# frutir.net
KiCad netlist of a schematic drawn in EAGLE
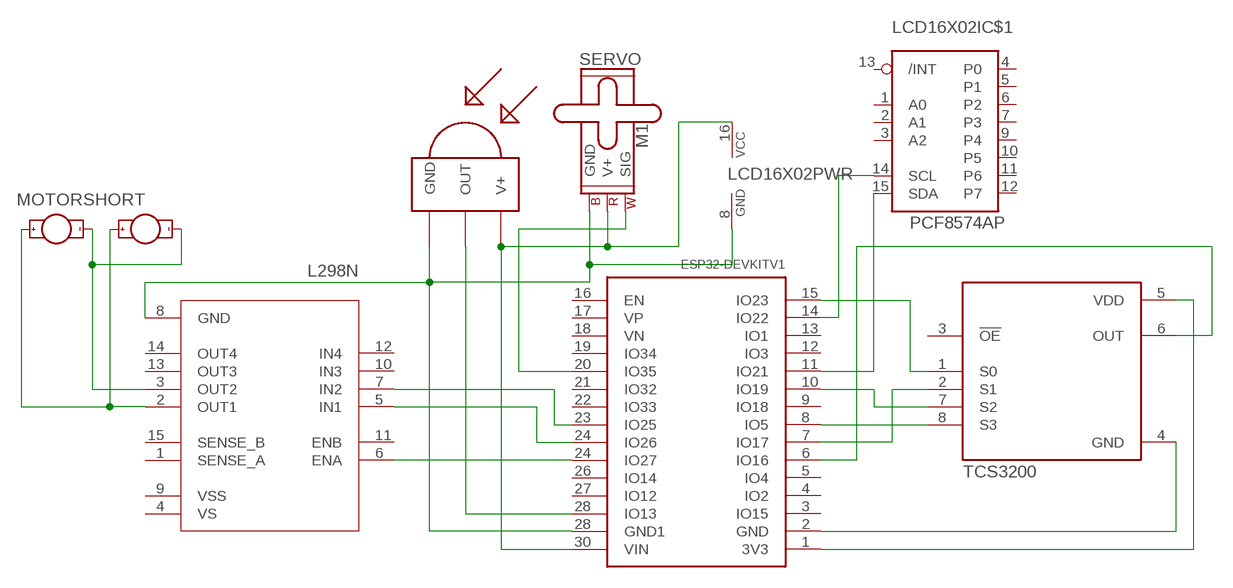
[diagram p0: schematic, sheet 1]

(export (version "E")
  (design (tool "Eeschema 10.0.6"))
  (components
    (comp (ref "LCD16X02")
      (value "PCF8574AP")
      (footprint "eagle-import:DIL16")
      (libsource (lib "eagle-import") (part "PCF8574AP"))
    )
    (comp (ref "M1")
      (value "SERVO")
      (footprint "eagle-import:1X03")
      (libsource (lib "eagle-import") (part "SERVO"))
    )
    (comp (ref "M2")
      (value "MOTORSHORT")
      (footprint "eagle-import:VIBE-MOTOR-10MM-SMD")
      (libsource (lib "eagle-import") (part "MOTORSHORT"))
    )
    (comp (ref "M3")
      (value "MOTORSHORT")
      (footprint "eagle-import:VIBE-MOTOR-10MM-SMD")
      (libsource (lib "eagle-import") (part "MOTORSHORT"))
    )
    (comp (ref "U$1")
      (value "ESP32DEVKITV1")
      (footprint "eagle-import:ESP32-DEVKITV1")
      (libsource (lib "eagle-import") (part "ESP32DEVKITV1"))
    )
    (comp (ref "U$2")
      (value "TSOP1830")
      (footprint "eagle-import:TSOP18XX")
      (libsource (lib "eagle-import") (part "TSOP1830"))
    )
    (comp (ref "U1")
      (value "TCS3200")
      (footprint "eagle-import:SOIC127P600X175-8N")
      (fields (field (name "MF") "ams"))
      (libsource (lib "eagle-import") (part "TCS3200"))
    )
    (comp (ref "U2")
      (value "L298N")
      (footprint "eagle-import:TO127P2020X500X2100-15")
      (fields (field (name "MF") "STMicroelectronics"))
      (libsource (lib "eagle-import") (part "L298N"))
    )
  )
  (nets
    (net (code "1") (name "/VS") (class "Default")
      (node (ref "U2") (pin "4") (pinfunction "VS_4") (pintype "power_in"))
    )
    (net (code "2") (name "Net-(LCD16X02A-SCL)") (class "Default")
      (node (ref "LCD16X02") (pin "14") (pinfunction "SCL_14") (pintype "input"))
      (node (ref "U$1") (pin "14") (pinfunction "IO22_14") (pintype "bidirectional"))
    )
    (net (code "3") (name "Net-(LCD16X02A-SDA)") (class "Default")
      (node (ref "LCD16X02") (pin "15") (pinfunction "SDA_15") (pintype "bidirectional"))
      (node (ref "U$1") (pin "11") (pinfunction "IO21_11") (pintype "bidirectional"))
    )
    (net (code "4") (name "Net-(LCD16X02B-GND)") (class "Default")
      (node (ref "LCD16X02") (pin "8") (pinfunction "GND_8") (pintype "power_in"))
      (node (ref "M1") (pin "3") (pinfunction "GND_3") (pintype "bidirectional"))
      (node (ref "U$1") (pin "28") (pinfunction "GND1_28") (pintype "bidirectional"))
      (node (ref "U$2") (pin "GND") (pinfunction "GND_GND") (pintype "bidirectional"))
      (node (ref "U2") (pin "8") (pinfunction "GND_8") (pintype "power_in"))
    )
    (net (code "5") (name "Net-(LCD16X02B-VCC)") (class "Default")
      (node (ref "LCD16X02") (pin "16") (pinfunction "VCC_16") (pintype "power_in"))
      (node (ref "M1") (pin "2") (pinfunction "V+_2") (pintype "bidirectional"))
      (node (ref "U$1") (pin "30") (pinfunction "VIN_30") (pintype "bidirectional"))
      (node (ref "U$2") (pin "VCC") (pinfunction "V+_VCC") (pintype "bidirectional"))
    )
    (net (code "6") (name "Net-(M1-SIG)") (class "Default")
      (node (ref "M1") (pin "1") (pinfunction "SIG_1") (pintype "bidirectional"))
      (node (ref "U$1") (pin "20") (pinfunction "IO35_20") (pintype "bidirectional"))
    )
    (net (code "7") (name "Net-(U$1-3V3)") (class "Default")
      (node (ref "U$1") (pin "1") (pinfunction "3V3_1") (pintype "bidirectional"))
      (node (ref "U1") (pin "5") (pinfunction "VDD_5") (pintype "power_in"))
    )
    (net (code "8") (name "Net-(U$1-GND)") (class "Default")
      (node (ref "U$1") (pin "2") (pinfunction "GND_2") (pintype "bidirectional"))
      (node (ref "U1") (pin "4") (pinfunction "GND_4") (pintype "power_in"))
    )
    (net (code "9") (name "Net-(U$1-IO5)") (class "Default")
      (node (ref "U$1") (pin "8") (pinfunction "IO5_8") (pintype "bidirectional"))
      (node (ref "U1") (pin "8") (pinfunction "S3_8") (pintype "input"))
    )
    (net (code "10") (name "Net-(U$1-IO13)") (class "Default")
      (node (ref "U$1") (pin "28") (pinfunction "IO13_28") (pintype "bidirectional"))
      (node (ref "U$2") (pin "OUT") (pinfunction "OUT_OUT") (pintype "bidirectional"))
    )
    (net (code "11") (name "Net-(U$1-IO16)") (class "Default")
      (node (ref "U$1") (pin "6") (pinfunction "IO16_6") (pintype "bidirectional"))
      (node (ref "U1") (pin "6") (pinfunction "OUT_6") (pintype "output"))
    )
    (net (code "12") (name "Net-(U$1-IO17)") (class "Default")
      (node (ref "U$1") (pin "7") (pinfunction "IO17_7") (pintype "bidirectional"))
      (node (ref "U1") (pin "2") (pinfunction "S1_2") (pintype "input"))
    )
    (net (code "13") (name "Net-(U$1-IO19)") (class "Default")
      (node (ref "U$1") (pin "10") (pinfunction "IO19_10") (pintype "bidirectional"))
      (node (ref "U1") (pin "7") (pinfunction "S2_7") (pintype "input"))
    )
    (net (code "14") (name "Net-(U$1-IO23)") (class "Default")
      (node (ref "U$1") (pin "15") (pinfunction "IO23_15") (pintype "bidirectional"))
      (node (ref "U1") (pin "1") (pinfunction "S0_1") (pintype "input"))
    )
    (net (code "15") (name "Net-(U$1-IO25)") (class "Default")
      (node (ref "U$1") (pin "23") (pinfunction "IO25_23") (pintype "bidirectional"))
      (node (ref "U2") (pin "7") (pinfunction "IN2_7") (pintype "input"))
    )
    (net (code "16") (name "Net-(U$1-IO26)") (class "Default")
      (node (ref "U$1") (pin "24") (pinfunction "IO26_24") (pintype "bidirectional"))
      (node (ref "U2") (pin "5") (pinfunction "IN1_5") (pintype "input"))
    )
    (net (code "17") (name "Net-(U$1-IO27)") (class "Default")
      (node (ref "U$1") (pin "24") (pinfunction "IO27_24") (pintype "bidirectional"))
      (node (ref "U2") (pin "6") (pinfunction "ENA_6") (pintype "input"))
    )
    (net (code "18") (name "Net-(U2-OUT1)") (class "Default")
      (node (ref "M2") (pin "+") (pinfunction "+_+") (pintype "bidirectional"))
      (node (ref "M3") (pin "+") (pinfunction "+_+") (pintype "bidirectional"))
      (node (ref "U2") (pin "2") (pinfunction "OUT1_2") (pintype "output"))
    )
    (net (code "19") (name "Net-(U2-OUT2)") (class "Default")
      (node (ref "M2") (pin "-") (pinfunction "-_-") (pintype "bidirectional"))
      (node (ref "M3") (pin "-") (pinfunction "-_-") (pintype "bidirectional"))
      (node (ref "U2") (pin "3") (pinfunction "OUT2_3") (pintype "output"))
    )
    (net (code "20") (name "unconnected-(LCD16X02A-A0-Pad1)") (class "Default")
      (node (ref "LCD16X02") (pin "1") (pinfunction "A0_1") (pintype "input"))
    )
    (net (code "21") (name "unconnected-(LCD16X02A-A1-Pad2)") (class "Default")
      (node (ref "LCD16X02") (pin "2") (pinfunction "A1_2") (pintype "input"))
    )
    (net (code "22") (name "unconnected-(LCD16X02A-A2-Pad3)") (class "Default")
      (node (ref "LCD16X02") (pin "3") (pinfunction "A2_3") (pintype "input"))
    )
    (net (code "23") (name "unconnected-(LCD16X02A-P0-Pad4)") (class "Default")
      (node (ref "LCD16X02") (pin "4") (pinfunction "P0_4") (pintype "bidirectional"))
    )
    (net (code "24") (name "unconnected-(LCD16X02A-P1-Pad5)") (class "Default")
      (node (ref "LCD16X02") (pin "5") (pinfunction "P1_5") (pintype "bidirectional"))
    )
    (net (code "25") (name "unconnected-(LCD16X02A-P2-Pad6)") (class "Default")
      (node (ref "LCD16X02") (pin "6") (pinfunction "P2_6") (pintype "bidirectional"))
    )
    (net (code "26") (name "unconnected-(LCD16X02A-P3-Pad7)") (class "Default")
      (node (ref "LCD16X02") (pin "7") (pinfunction "P3_7") (pintype "bidirectional"))
    )
    (net (code "27") (name "unconnected-(LCD16X02A-P4-Pad9)") (class "Default")
      (node (ref "LCD16X02") (pin "9") (pinfunction "P4_9") (pintype "bidirectional"))
    )
    (net (code "28") (name "unconnected-(LCD16X02A-P5-Pad10)") (class "Default")
      (node (ref "LCD16X02") (pin "10") (pinfunction "P5_10") (pintype "bidirectional"))
    )
    (net (code "29") (name "unconnected-(LCD16X02A-P6-Pad11)") (class "Default")
      (node (ref "LCD16X02") (pin "11") (pinfunction "P6_11") (pintype "bidirectional"))
    )
    (net (code "30") (name "unconnected-(LCD16X02A-P7-Pad12)") (class "Default")
      (node (ref "LCD16X02") (pin "12") (pinfunction "P7_12") (pintype "bidirectional"))
    )
    (net (code "31") (name "unconnected-(LCD16X02A-{slash}INT-Pad13)") (class "Default")
      (node (ref "LCD16X02") (pin "13") (pinfunction "/INT_13") (pintype "output"))
    )
    (net (code "32") (name "unconnected-(U$1-EN-Pad16)") (class "Default")
      (node (ref "U$1") (pin "16") (pinfunction "EN_16") (pintype "bidirectional"))
    )
    (net (code "33") (name "unconnected-(U$1-IO1-Pad13)") (class "Default")
      (node (ref "U$1") (pin "13") (pinfunction "IO1_13") (pintype "bidirectional"))
    )
    (net (code "34") (name "unconnected-(U$1-IO2-Pad4)") (class "Default")
      (node (ref "U$1") (pin "4") (pinfunction "IO2_4") (pintype "bidirectional"))
    )
    (net (code "35") (name "unconnected-(U$1-IO3-Pad12)") (class "Default")
      (node (ref "U$1") (pin "12") (pinfunction "IO3_12") (pintype "bidirectional"))
    )
    (net (code "36") (name "unconnected-(U$1-IO4-Pad5)") (class "Default")
      (node (ref "U$1") (pin "5") (pinfunction "IO4_5") (pintype "bidirectional"))
    )
    (net (code "37") (name "unconnected-(U$1-IO12-Pad27)") (class "Default")
      (node (ref "U$1") (pin "27") (pinfunction "IO12_27") (pintype "bidirectional"))
    )
    (net (code "38") (name "unconnected-(U$1-IO14-Pad26)") (class "Default")
      (node (ref "U$1") (pin "26") (pinfunction "IO14_26") (pintype "bidirectional"))
    )
    (net (code "39") (name "unconnected-(U$1-IO15-Pad3)") (class "Default")
      (node (ref "U$1") (pin "3") (pinfunction "IO15_3") (pintype "bidirectional"))
    )
    (net (code "40") (name "unconnected-(U$1-IO18-Pad9)") (class "Default")
      (node (ref "U$1") (pin "9") (pinfunction "IO18_9") (pintype "bidirectional"))
    )
    (net (code "41") (name "unconnected-(U$1-IO32-Pad21)") (class "Default")
      (node (ref "U$1") (pin "21") (pinfunction "IO32_21") (pintype "bidirectional"))
    )
    (net (code "42") (name "unconnected-(U$1-IO33-Pad22)") (class "Default")
      (node (ref "U$1") (pin "22") (pinfunction "IO33_22") (pintype "bidirectional"))
    )
    (net (code "43") (name "unconnected-(U$1-IO34-Pad19)") (class "Default")
      (node (ref "U$1") (pin "19") (pinfunction "IO34_19") (pintype "bidirectional"))
    )
    (net (code "44") (name "unconnected-(U$1-VN-Pad18)") (class "Default")
      (node (ref "U$1") (pin "18") (pinfunction "VN_18") (pintype "bidirectional"))
    )
    (net (code "45") (name "unconnected-(U$1-VP-Pad17)") (class "Default")
      (node (ref "U$1") (pin "17") (pinfunction "VP_17") (pintype "bidirectional"))
    )
    (net (code "46") (name "unconnected-(U1-~{OE}-Pad3)") (class "Default")
      (node (ref "U1") (pin "3") (pinfunction "~{OE}_3") (pintype "input"))
    )
    (net (code "47") (name "unconnected-(U2-ENB-Pad11)") (class "Default")
      (node (ref "U2") (pin "11") (pinfunction "ENB_11") (pintype "input"))
    )
    (net (code "48") (name "unconnected-(U2-IN3-Pad10)") (class "Default")
      (node (ref "U2") (pin "10") (pinfunction "IN3_10") (pintype "input"))
    )
    (net (code "49") (name "unconnected-(U2-IN4-Pad12)") (class "Default")
      (node (ref "U2") (pin "12") (pinfunction "IN4_12") (pintype "input"))
    )
    (net (code "50") (name "unconnected-(U2-OUT3-Pad13)") (class "Default")
      (node (ref "U2") (pin "13") (pinfunction "OUT3_13") (pintype "output"))
    )
    (net (code "51") (name "unconnected-(U2-OUT4-Pad14)") (class "Default")
      (node (ref "U2") (pin "14") (pinfunction "OUT4_14") (pintype "output"))
    )
    (net (code "52") (name "unconnected-(U2-SENSE_A-Pad1)") (class "Default")
      (node (ref "U2") (pin "1") (pinfunction "SENSE_A_1") (pintype "passive"))
    )
    (net (code "53") (name "unconnected-(U2-SENSE_B-Pad15)") (class "Default")
      (node (ref "U2") (pin "15") (pinfunction "SENSE_B_15") (pintype "passive"))
    )
    (net (code "54") (name "unconnected-(U2-VSS-Pad9)") (class "Default")
      (node (ref "U2") (pin "9") (pinfunction "VSS_9") (pintype "input"))
    )
  )
)
